# PCB_Telemetria_2020.net
KiCad netlist of a schematic drawn in EAGLE
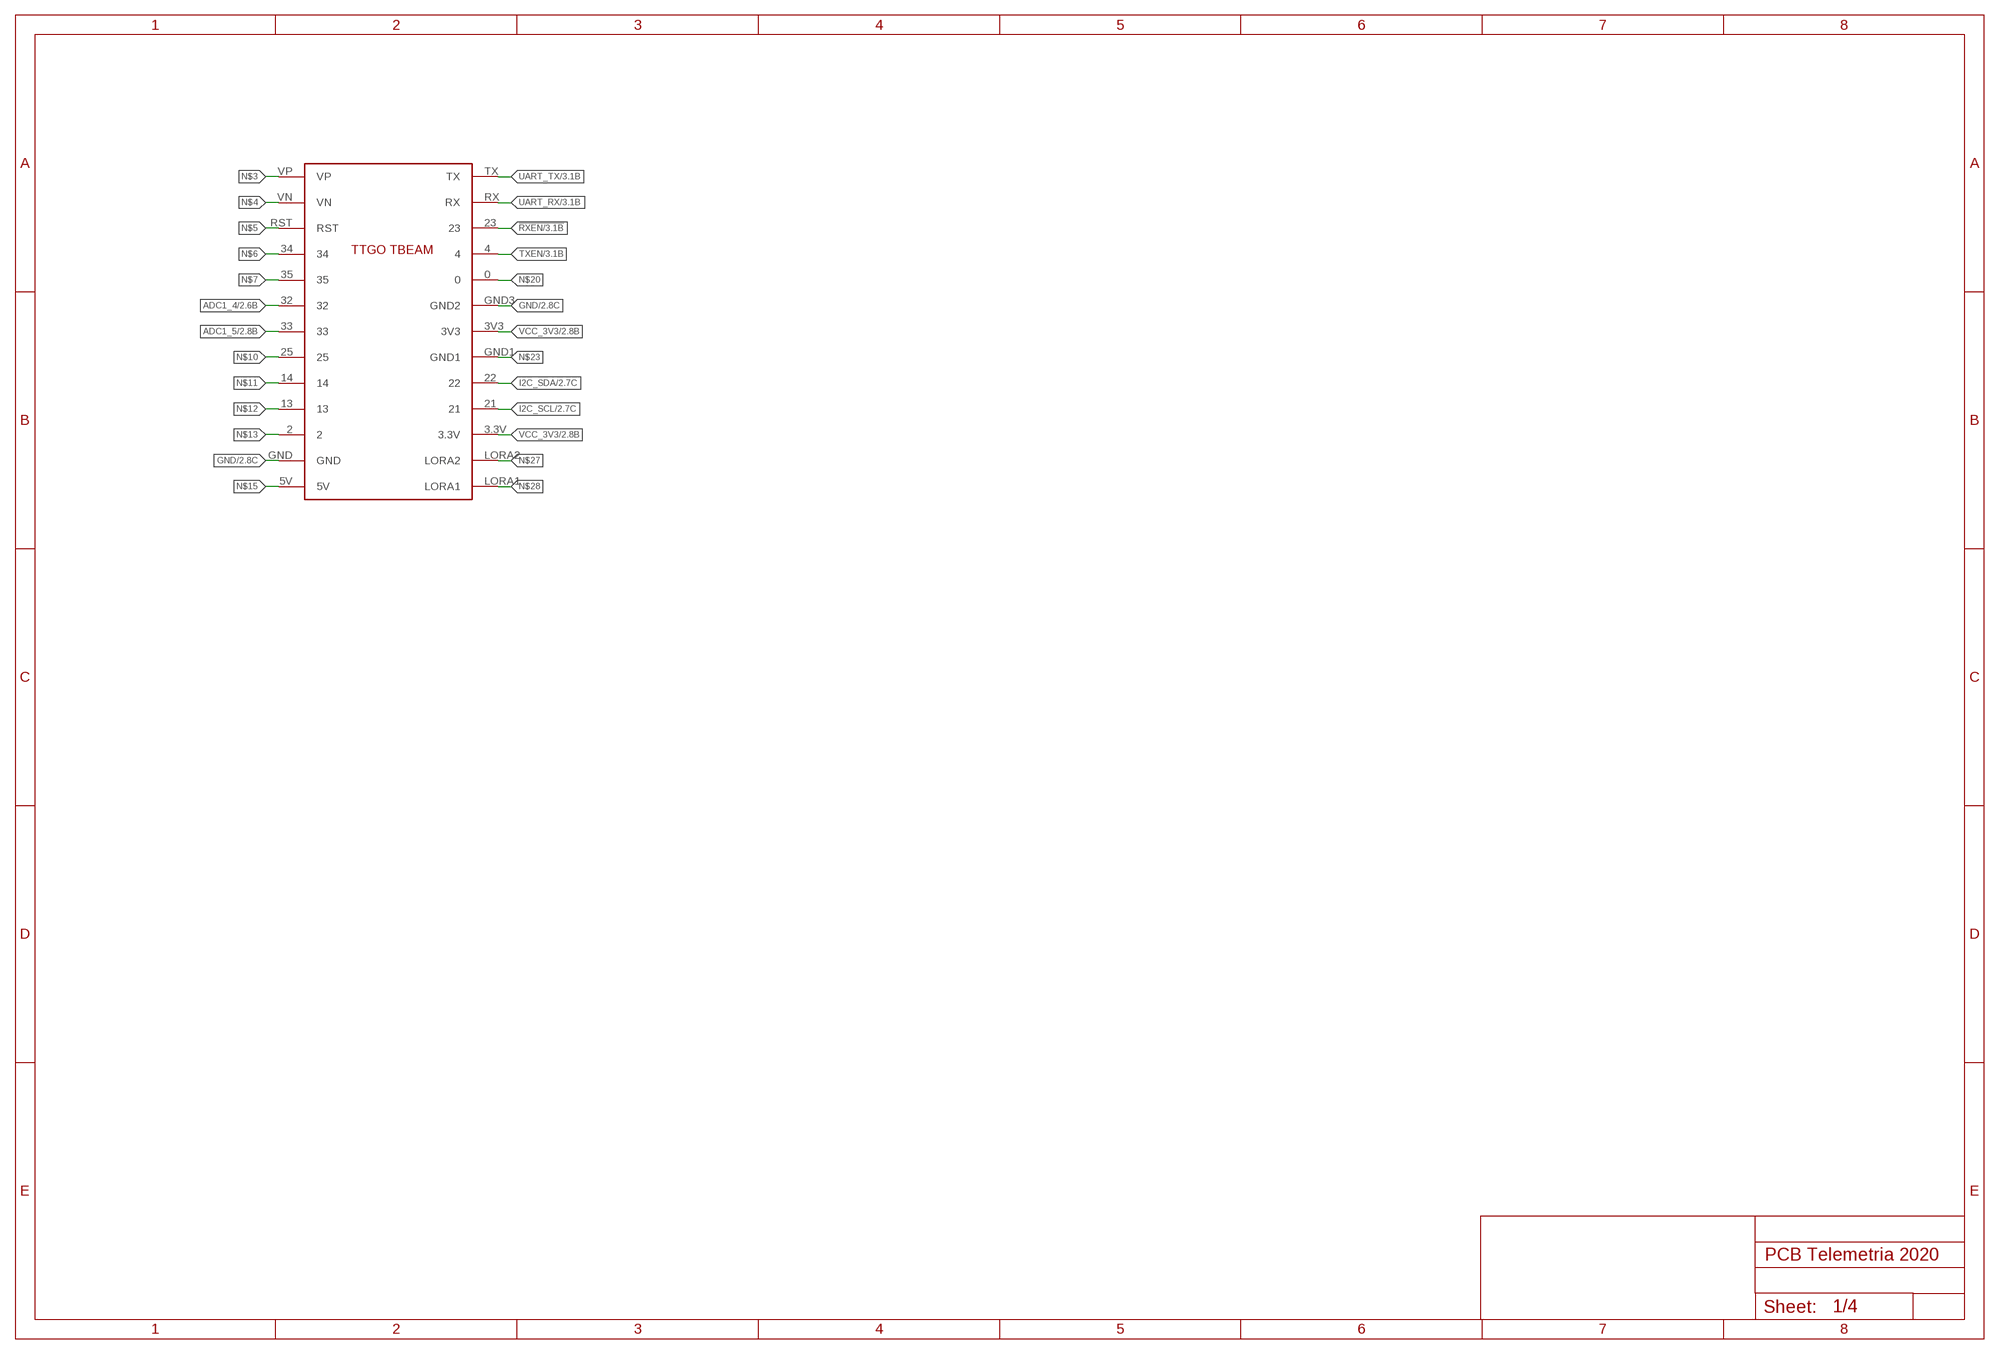
[diagram p0: schematic, sheet 1]
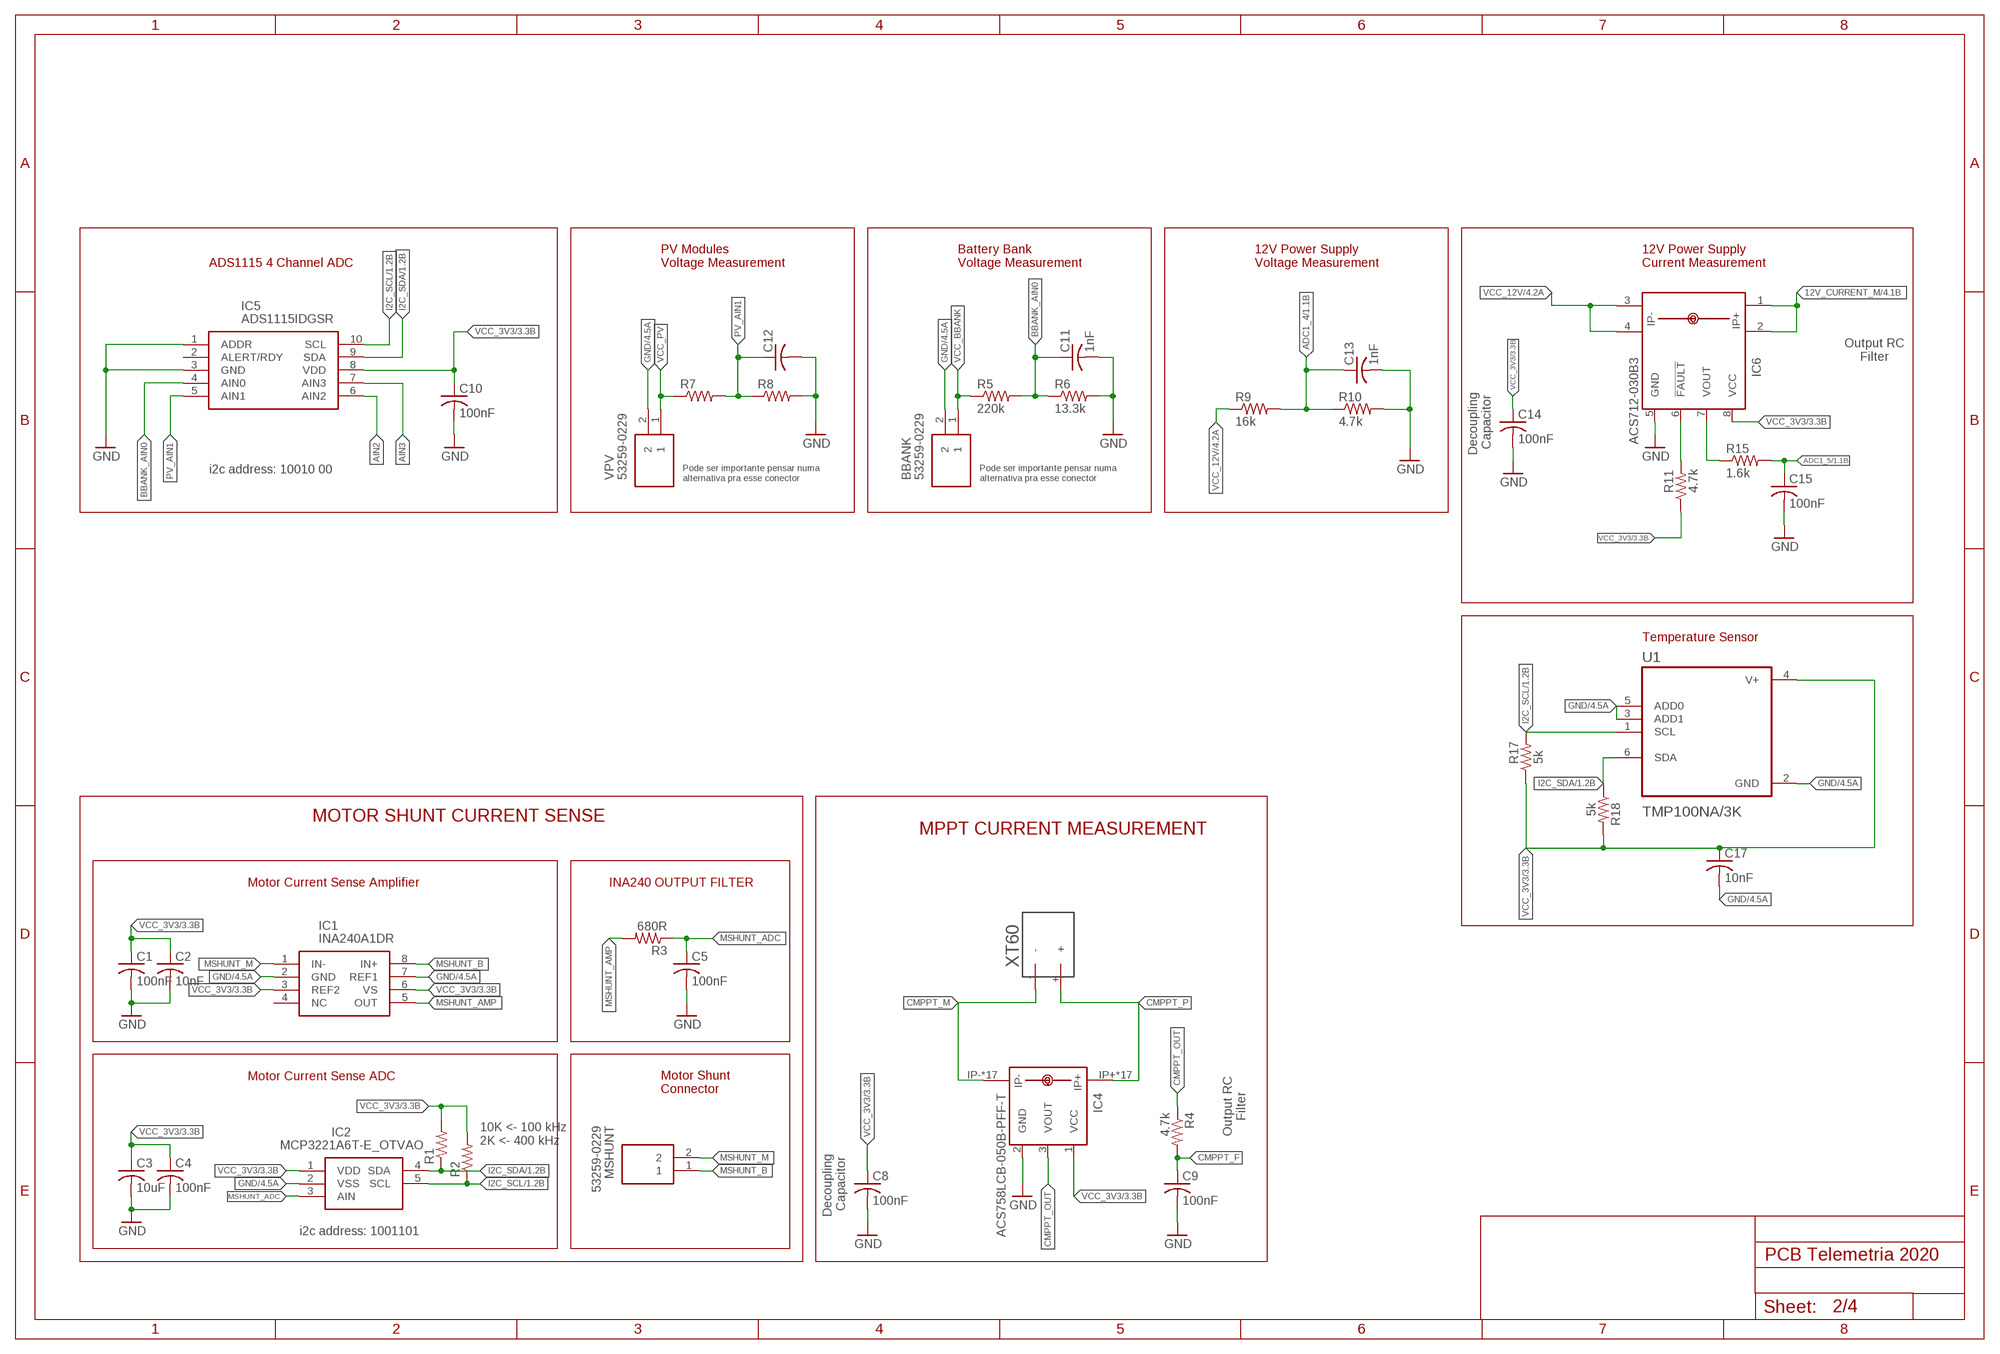
[diagram p1: schematic, sheet 2]
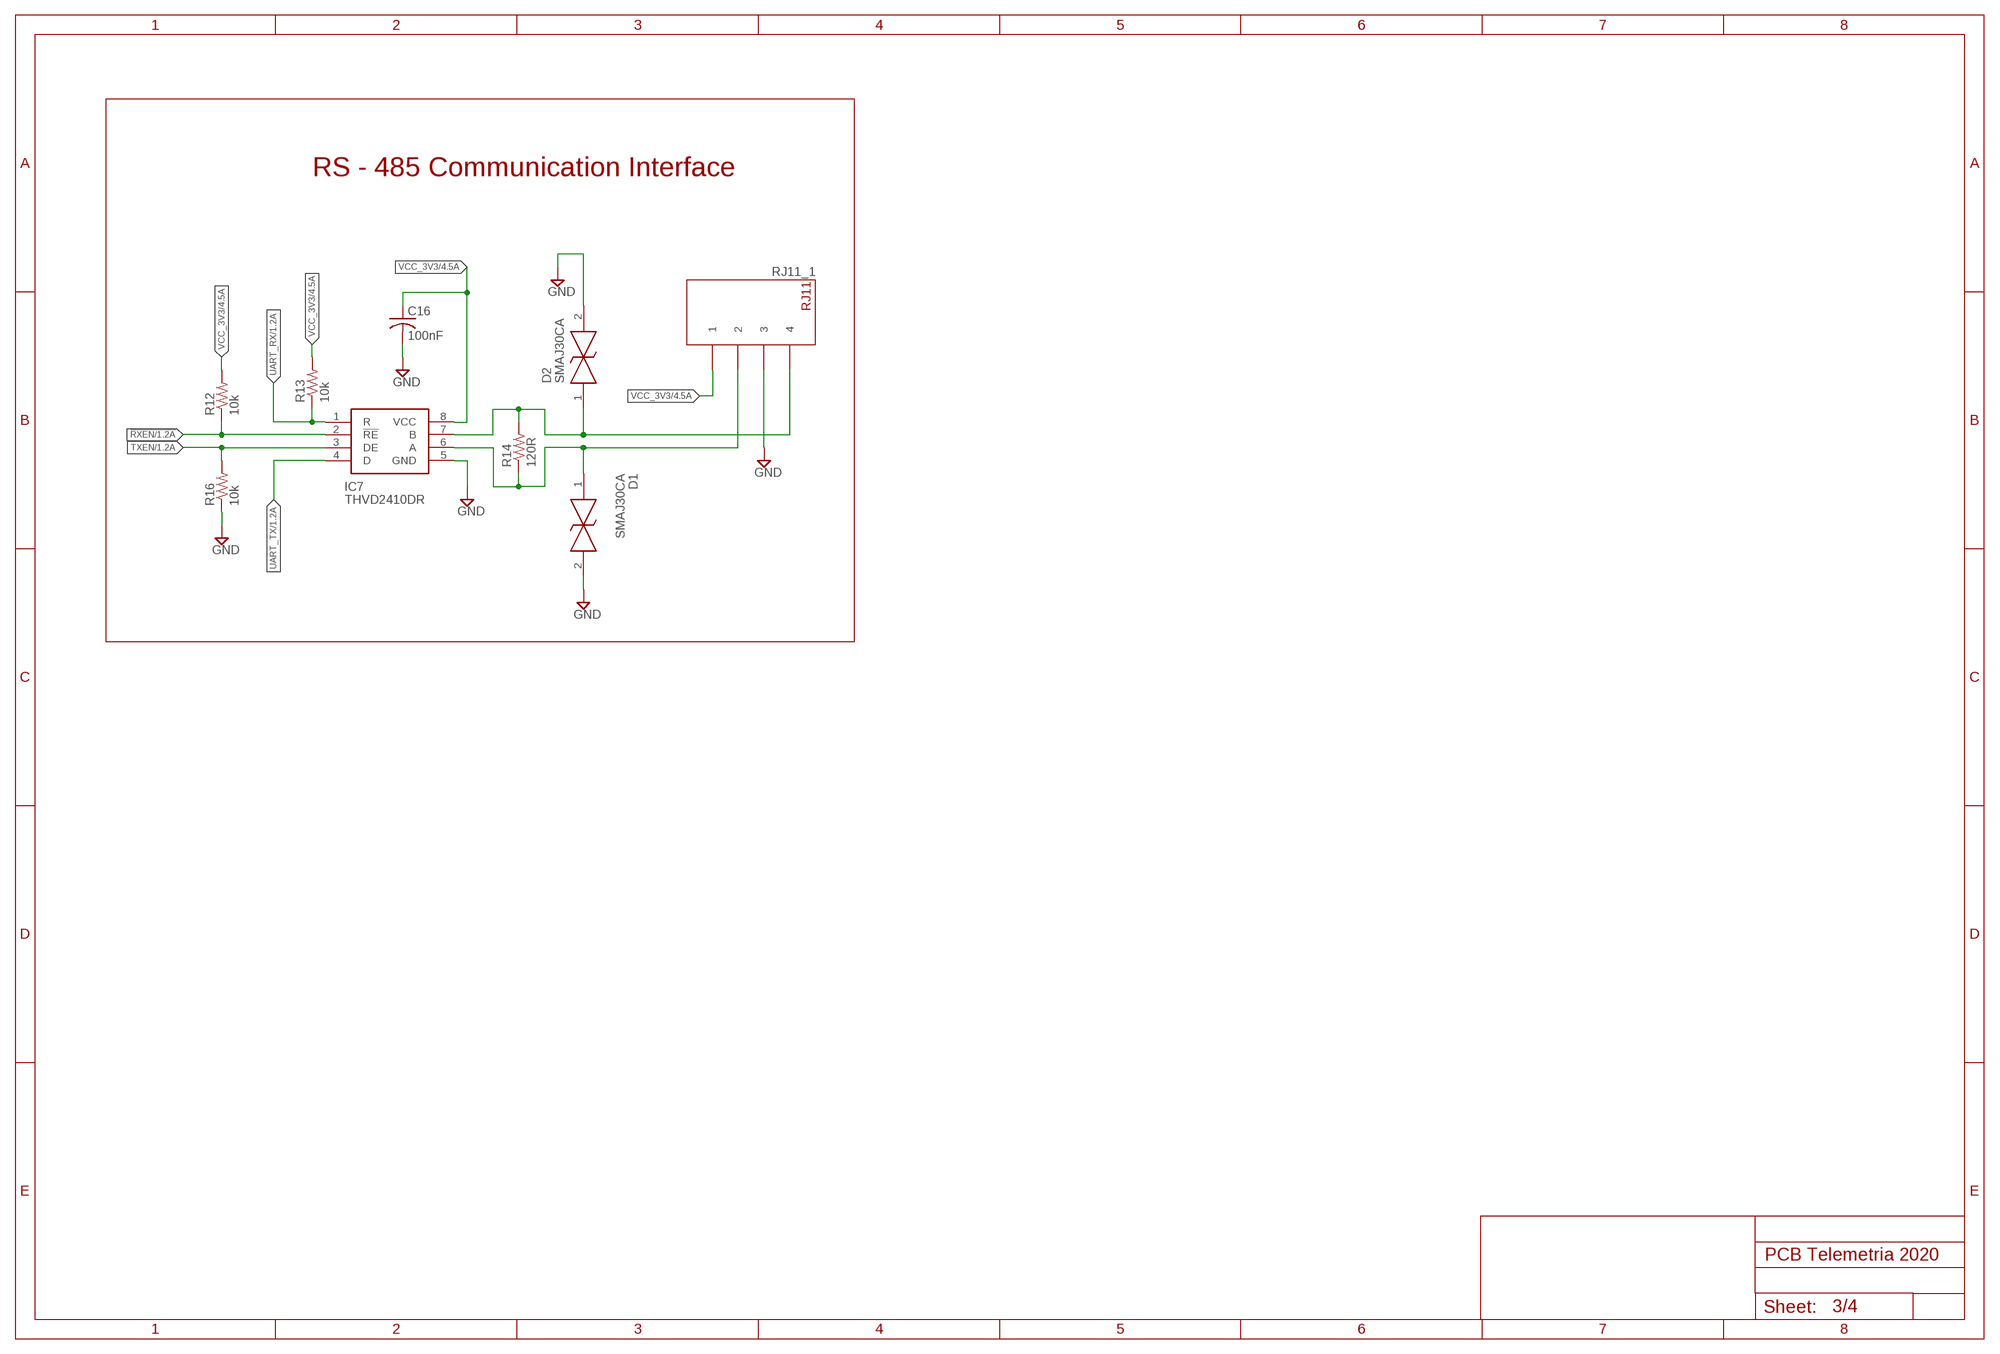
[diagram p2: schematic, sheet 3]
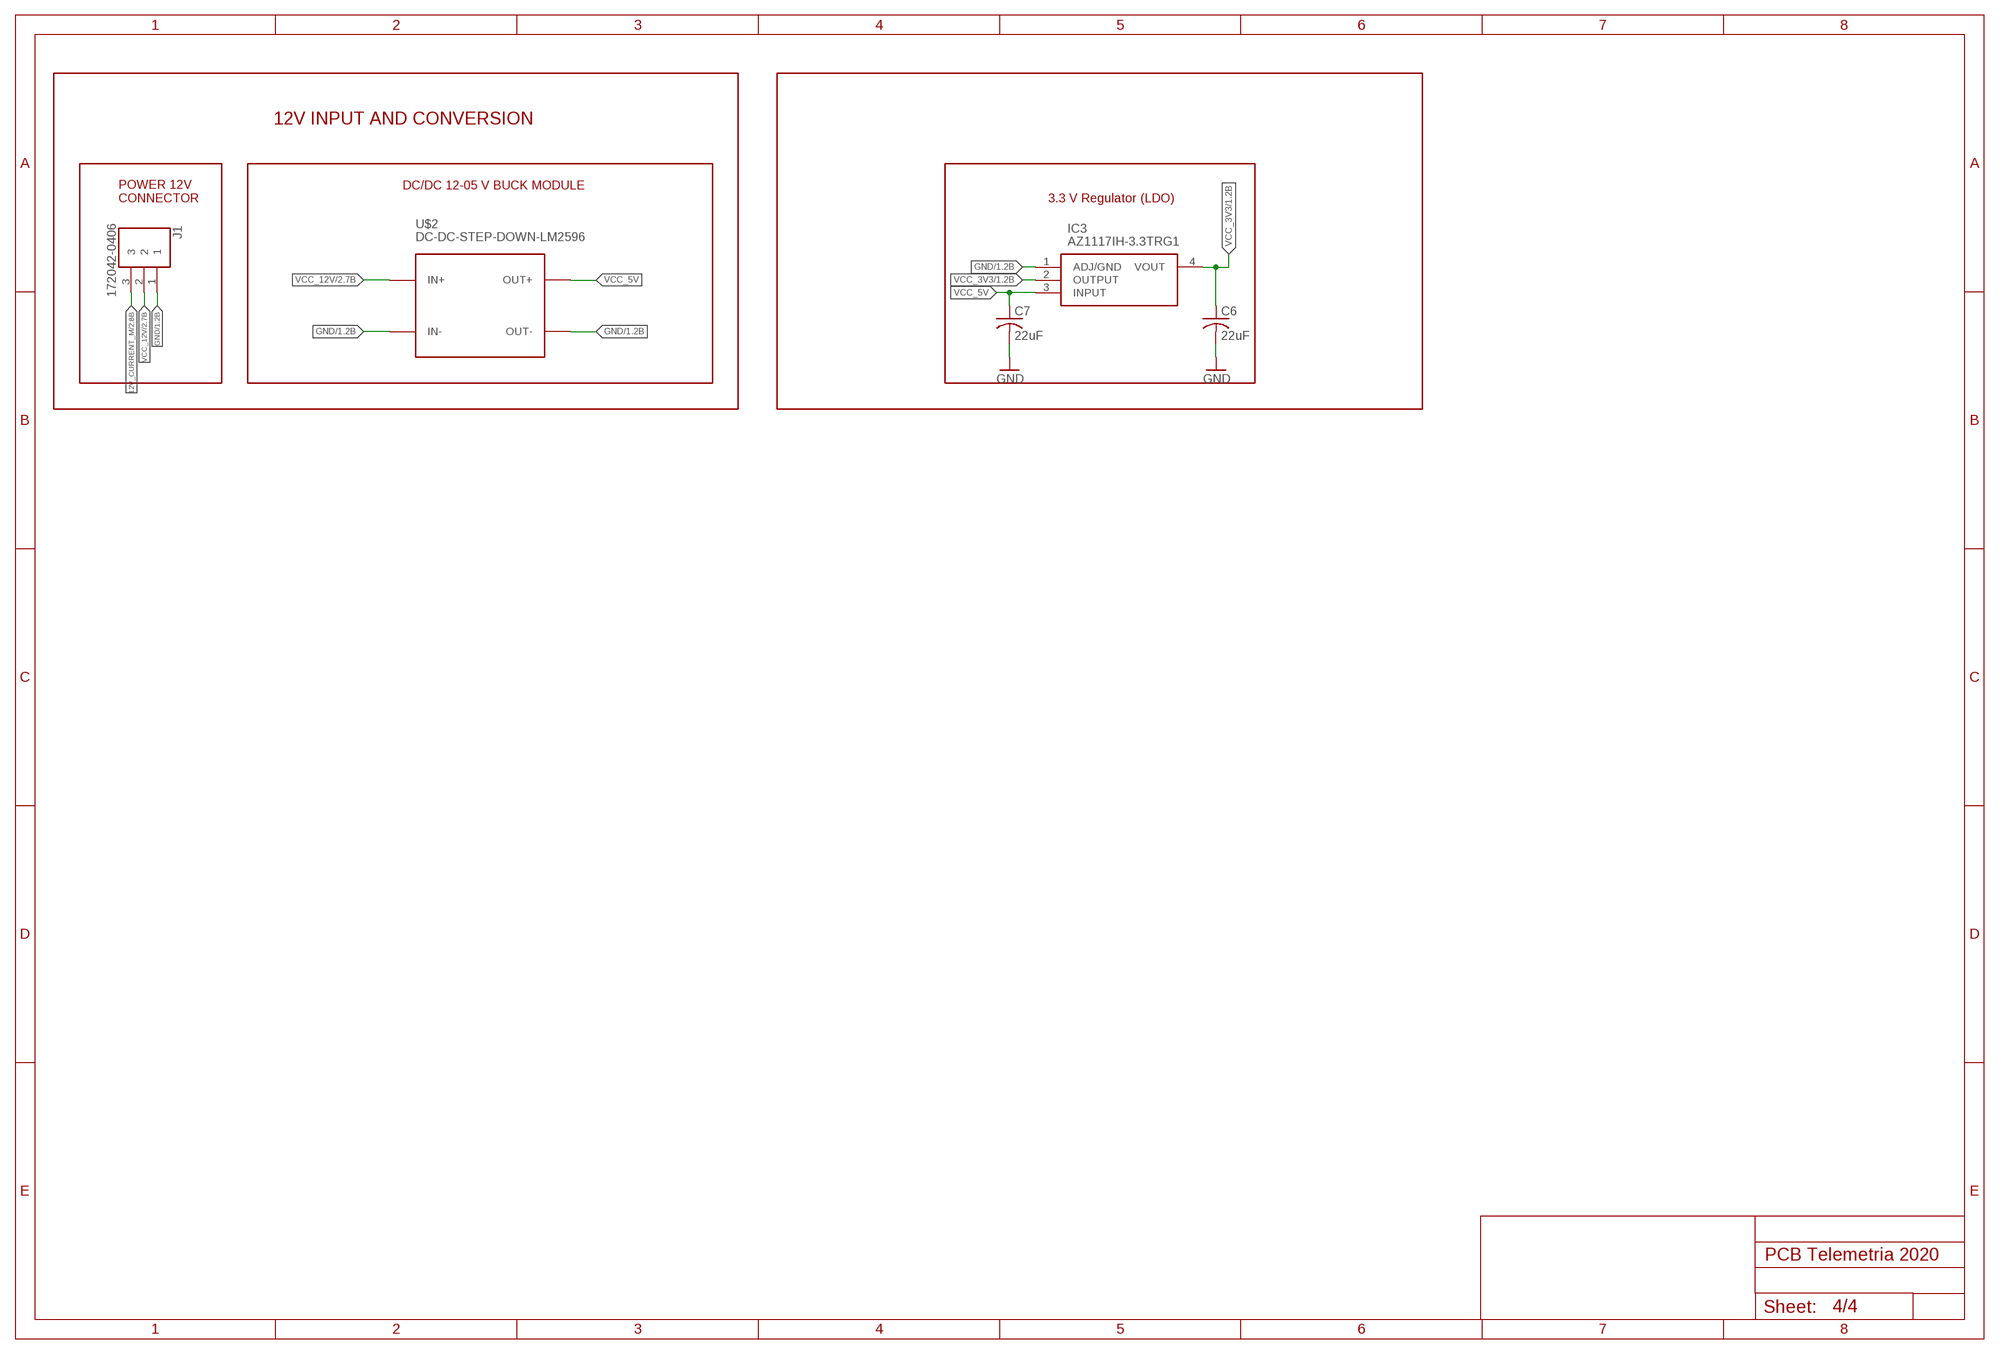
[diagram p3: schematic, sheet 4]

(export (version "E")
  (design (tool "Eeschema 10.0.6"))
  (components
    (comp (ref "BBANK")
      (value "53259-0229")
      (footprint "eagle-import:0532590229")
      (fields (field (name "MOUSER_PART_NUMBER") "538-53259-0229"))
      (libsource (lib "eagle-import") (part "53259-0229"))
    )
    (comp (ref "C1")
      (value "100nF")
      (footprint "eagle-import:C0805")
      (libsource (lib "eagle-import") (part "C-USC0805"))
    )
    (comp (ref "C2")
      (value "10nF")
      (footprint "eagle-import:C0805")
      (libsource (lib "eagle-import") (part "C-USC0805"))
    )
    (comp (ref "C3")
      (value "10uF")
      (footprint "eagle-import:C0805")
      (libsource (lib "eagle-import") (part "C-USC0805"))
    )
    (comp (ref "C4")
      (value "100nF")
      (footprint "eagle-import:C0805")
      (libsource (lib "eagle-import") (part "C-USC0805"))
    )
    (comp (ref "C5")
      (value "100nF")
      (footprint "eagle-import:C0805")
      (libsource (lib "eagle-import") (part "C-USC0805"))
    )
    (comp (ref "C8")
      (value "100nF")
      (footprint "eagle-import:C0805")
      (libsource (lib "eagle-import") (part "C-USC0805"))
    )
    (comp (ref "C9")
      (value "100nF")
      (footprint "eagle-import:C0805")
      (libsource (lib "eagle-import") (part "C-USC0805"))
    )
    (comp (ref "C10")
      (value "100nF")
      (footprint "eagle-import:C0805")
      (libsource (lib "eagle-import") (part "C-USC0805"))
    )
    (comp (ref "C11")
      (value "1nF")
      (footprint "eagle-import:C0805")
      (libsource (lib "eagle-import") (part "C-USC0805"))
    )
    (comp (ref "C12")
      (value "C-USC0805")
      (footprint "eagle-import:C0805")
      (libsource (lib "eagle-import") (part "C-USC0805"))
    )
    (comp (ref "C13")
      (value "1nF")
      (footprint "eagle-import:C0805")
      (libsource (lib "eagle-import") (part "C-USC0805"))
    )
    (comp (ref "C14")
      (value "100nF")
      (footprint "eagle-import:C0805")
      (libsource (lib "eagle-import") (part "C-USC0805"))
    )
    (comp (ref "C15")
      (value "100nF")
      (footprint "eagle-import:C0805")
      (libsource (lib "eagle-import") (part "C-USC0805"))
    )
    (comp (ref "C17")
      (value "10nF")
      (footprint "eagle-import:C0805")
      (libsource (lib "eagle-import") (part "C-USC0805"))
    )
    (comp (ref "IC1")
      (value "INA240A1DR")
      (footprint "eagle-import:SOIC127P600X175-8N")
      (fields (field (name "MOUSER_PART_NUMBER") "595-INA240A1DR"))
      (libsource (lib "eagle-import") (part "INA240A1DR"))
    )
    (comp (ref "IC2")
      (value "MCP3221A6T-E_OTVAO")
      (footprint "eagle-import:SOT95P280X145-5N")
      (fields
        (field (name "MANUFACTURER_PART_NUMBER") "MCP3221A6T-E/OTVAO")
        (field (name "MOUSER_PART_NUMBER") "579-MCP3221A6TEOTVAO")
      )
      (libsource (lib "eagle-import") (part "MCP3221A6T-E_OTVAO"))
    )
    (comp (ref "IC4")
      (value "ACS758LCB-050B-PFF-T")
      (footprint "eagle-import:CB-PFF")
      (libsource (lib "eagle-import") (part "ACS758LCB-050B-PFF-T"))
    )
    (comp (ref "IC5")
      (value "ADS1115IDGSR")
      (footprint "eagle-import:SOP50P490X110-10N")
      (fields (field (name "MOUSER_PART_NUMBER") "595-ADS1115IDGSR"))
      (libsource (lib "eagle-import") (part "ADS1115IDGSR"))
    )
    (comp (ref "IC6")
      (value "ACS712-030B3")
      (footprint "eagle-import:SOIC8")
      (libsource (lib "eagle-import") (part "ACS712-LC"))
    )
    (comp (ref "MSHUNT")
      (value "53259-0229")
      (footprint "eagle-import:0532590229")
      (fields (field (name "MOUSER_PART_NUMBER") "538-53259-0229"))
      (libsource (lib "eagle-import") (part "53259-0229"))
    )
    (comp (ref "R1")
      (value "R-US_R0805")
      (footprint "eagle-import:R0805")
      (libsource (lib "eagle-import") (part "R-US_R0805"))
    )
    (comp (ref "R2")
      (value "R-US_R0805")
      (footprint "eagle-import:R0805")
      (libsource (lib "eagle-import") (part "R-US_R0805"))
    )
    (comp (ref "R3")
      (value "680R")
      (footprint "eagle-import:R0805")
      (libsource (lib "eagle-import") (part "R-US_R0805"))
    )
    (comp (ref "R4")
      (value "4.7k")
      (footprint "eagle-import:R0805")
      (libsource (lib "eagle-import") (part "R-US_R0805"))
    )
    (comp (ref "R5")
      (value "220k")
      (footprint "eagle-import:R0805")
      (libsource (lib "eagle-import") (part "R-US_R0805"))
    )
    (comp (ref "R6")
      (value "13.3k")
      (footprint "eagle-import:R0805")
      (libsource (lib "eagle-import") (part "R-US_R0805"))
    )
    (comp (ref "R7")
      (value "R-US_R0805")
      (footprint "eagle-import:R0805")
      (libsource (lib "eagle-import") (part "R-US_R0805"))
    )
    (comp (ref "R8")
      (value "R-US_R0805")
      (footprint "eagle-import:R0805")
      (libsource (lib "eagle-import") (part "R-US_R0805"))
    )
    (comp (ref "R9")
      (value "16k")
      (footprint "eagle-import:R0805")
      (libsource (lib "eagle-import") (part "R-US_R0805"))
    )
    (comp (ref "R10")
      (value "4.7k")
      (footprint "eagle-import:R0805")
      (libsource (lib "eagle-import") (part "R-US_R0805"))
    )
    (comp (ref "R11")
      (value "4.7k")
      (footprint "eagle-import:R0805")
      (libsource (lib "eagle-import") (part "R-US_R0805"))
    )
    (comp (ref "R15")
      (value "1.6k")
      (footprint "eagle-import:R0805")
      (libsource (lib "eagle-import") (part "R-US_R0805"))
    )
    (comp (ref "R17")
      (value "5k")
      (footprint "eagle-import:R0805")
      (libsource (lib "eagle-import") (part "R-US_R0805"))
    )
    (comp (ref "R18")
      (value "5k")
      (footprint "eagle-import:R0805")
      (libsource (lib "eagle-import") (part "R-US_R0805"))
    )
    (comp (ref "U$3")
      (value "XT60")
      (footprint "eagle-import:XT60")
      (libsource (lib "eagle-import") (part "XT60"))
    )
    (comp (ref "U1")
      (value "TMP100NA/3K")
      (footprint "eagle-import:SOT95P280X145-6N")
      (fields (field (name "MF") "Texas Instruments"))
      (libsource (lib "eagle-import") (part "TMP100NA/3K"))
    )
    (comp (ref "VPV")
      (value "53259-0229")
      (footprint "eagle-import:0532590229")
      (fields (field (name "MOUSER_PART_NUMBER") "538-53259-0229"))
      (libsource (lib "eagle-import") (part "53259-0229"))
    )
    (comp (ref "U$1")
      (value "TTGOBEAM")
      (footprint "eagle-import:TTGOBEAM")
      (libsource (lib "eagle-import") (part "TTGOBEAM"))
    )
    (comp (ref "C6")
      (value "22uF")
      (footprint "eagle-import:C0805")
      (libsource (lib "eagle-import") (part "C-USC0805"))
    )
    (comp (ref "C7")
      (value "22uF")
      (footprint "eagle-import:C0805")
      (libsource (lib "eagle-import") (part "C-USC0805"))
    )
    (comp (ref "IC3")
      (value "AZ1117IH-3.3TRG1")
      (footprint "eagle-import:SOT230P700X170-4N")
      (fields (field (name "MOUSER_PART_NUMBER") "621-AZ1117IH-3.3TRG1"))
      (libsource (lib "eagle-import") (part "AZ1117IH-3.3TRG1"))
    )
    (comp (ref "J1")
      (value "172042-0406")
      (footprint "eagle-import:MOLEX_172042-0406")
      (fields (field (name "MF") "Molex") (field (name "MP") "172042-0302"))
      (libsource (lib "eagle-import") (part "172042-0406"))
    )
    (comp (ref "U$2")
      (value "DC-DC-STEP-DOWN-LM2596")
      (footprint "eagle-import:DC-DC-STEP-DOWN-LM2596")
      (libsource (lib "eagle-import") (part "DC-DC-STEP-DOWN-LM2596"))
    )
    (comp (ref "C16")
      (value "100nF")
      (footprint "eagle-import:C0805")
      (libsource (lib "eagle-import") (part "C-USC0805"))
    )
    (comp (ref "D1")
      (value "SMAJ30CA")
      (footprint "eagle-import:DIONM5026X229N")
      (fields (field (name "MOUSER_PART_NUMBER") "576-SMAJ30CA"))
      (libsource (lib "eagle-import") (part "SMAJ30CA"))
    )
    (comp (ref "D2")
      (value "SMAJ30CA")
      (footprint "eagle-import:DIONM5026X229N")
      (fields (field (name "MOUSER_PART_NUMBER") "576-SMAJ30CA"))
      (libsource (lib "eagle-import") (part "SMAJ30CA"))
    )
    (comp (ref "IC7")
      (value "THVD2410DR")
      (footprint "eagle-import:SOIC127P600X175-8N")
      (fields (field (name "MOUSER_PART_NUMBER") "595-THVD2410DR"))
      (libsource (lib "eagle-import") (part "THVD2410DR"))
    )
    (comp (ref "R12")
      (value "10k")
      (footprint "eagle-import:M0805")
      (libsource (lib "eagle-import") (part "R-US_M0805"))
    )
    (comp (ref "R13")
      (value "10k")
      (footprint "eagle-import:M0805")
      (libsource (lib "eagle-import") (part "R-US_M0805"))
    )
    (comp (ref "R14")
      (value "120R")
      (footprint "eagle-import:M0805")
      (libsource (lib "eagle-import") (part "R-US_M0805"))
    )
    (comp (ref "R16")
      (value "10k")
      (footprint "eagle-import:M0805")
      (libsource (lib "eagle-import") (part "R-US_M0805"))
    )
    (comp (ref "RJ11_1")
      (value "TFC44")
      (footprint "eagle-import:TFC44")
      (libsource (lib "eagle-import") (part "TFC44"))
    )
  )
  (nets
    (net (code "1") (name "12V_CURRENT_M") (class "Default")
      (node (ref "IC6") (pin "1") (pinfunction "IP+_1") (pintype "passive"))
      (node (ref "IC6") (pin "2") (pinfunction "IP+1_2") (pintype "passive"))
      (node (ref "J1") (pin "3") (pinfunction "3_3") (pintype "passive"))
    )
    (net (code "2") (name "ADC1_4") (class "Default")
      (node (ref "C13") (pin "1") (pinfunction "1_1") (pintype "passive"))
      (node (ref "R10") (pin "1") (pinfunction "1_1") (pintype "passive"))
      (node (ref "R9") (pin "2") (pinfunction "2_2") (pintype "passive"))
      (node (ref "U$1") (pin "32") (pinfunction "32_32") (pintype "bidirectional"))
    )
    (net (code "3") (name "ADC1_5") (class "Default")
      (node (ref "C15") (pin "1") (pinfunction "1_1") (pintype "passive"))
      (node (ref "R15") (pin "2") (pinfunction "2_2") (pintype "passive"))
      (node (ref "U$1") (pin "33") (pinfunction "33_33") (pintype "bidirectional"))
    )
    (net (code "4") (name "AIN2") (class "Default")
      (node (ref "IC5") (pin "6") (pinfunction "AIN2_6") (pintype "bidirectional"))
    )
    (net (code "5") (name "AIN3") (class "Default")
      (node (ref "IC5") (pin "7") (pinfunction "AIN3_7") (pintype "bidirectional"))
    )
    (net (code "6") (name "BBANK_AIN0") (class "Default")
      (node (ref "C11") (pin "1") (pinfunction "1_1") (pintype "passive"))
      (node (ref "IC5") (pin "4") (pinfunction "AIN0_4") (pintype "bidirectional"))
      (node (ref "R5") (pin "2") (pinfunction "2_2") (pintype "passive"))
      (node (ref "R6") (pin "1") (pinfunction "1_1") (pintype "passive"))
    )
    (net (code "7") (name "CMPPT_F") (class "Default")
      (node (ref "C9") (pin "1") (pinfunction "1_1") (pintype "passive"))
      (node (ref "R4") (pin "2") (pinfunction "2_2") (pintype "passive"))
    )
    (net (code "8") (name "CMPPT_M") (class "Default")
      (node (ref "IC4") (pin "IP-") (pinfunction "IP-_IP-") (pintype "passive"))
      (node (ref "IC4") (pin "IP-@10") (pinfunction "IP-_IP-@10") (pintype "passive"))
      (node (ref "IC4") (pin "IP-@11") (pinfunction "IP-_IP-@11") (pintype "passive"))
      (node (ref "IC4") (pin "IP-@12") (pinfunction "IP-_IP-@12") (pintype "passive"))
      (node (ref "IC4") (pin "IP-@13") (pinfunction "IP-_IP-@13") (pintype "passive"))
      (node (ref "IC4") (pin "IP-@14") (pinfunction "IP-_IP-@14") (pintype "passive"))
      (node (ref "IC4") (pin "IP-@15") (pinfunction "IP-_IP-@15") (pintype "passive"))
      (node (ref "IC4") (pin "IP-@16") (pinfunction "IP-_IP-@16") (pintype "passive"))
      (node (ref "IC4") (pin "IP-@17") (pinfunction "IP-_IP-@17") (pintype "passive"))
      (node (ref "IC4") (pin "IP-@2") (pinfunction "IP-_IP-@2") (pintype "passive"))
      (node (ref "IC4") (pin "IP-@3") (pinfunction "IP-_IP-@3") (pintype "passive"))
      (node (ref "IC4") (pin "IP-@4") (pinfunction "IP-_IP-@4") (pintype "passive"))
      (node (ref "IC4") (pin "IP-@5") (pinfunction "IP-_IP-@5") (pintype "passive"))
      (node (ref "IC4") (pin "IP-@6") (pinfunction "IP-_IP-@6") (pintype "passive"))
      (node (ref "IC4") (pin "IP-@7") (pinfunction "IP-_IP-@7") (pintype "passive"))
      (node (ref "IC4") (pin "IP-@8") (pinfunction "IP-_IP-@8") (pintype "passive"))
      (node (ref "IC4") (pin "IP-@9") (pinfunction "IP-_IP-@9") (pintype "passive"))
      (node (ref "U$3") (pin "-") (pinfunction "-_-") (pintype "bidirectional"))
    )
    (net (code "9") (name "CMPPT_OUT") (class "Default")
      (node (ref "IC4") (pin "3") (pinfunction "VOUT_3") (pintype "output"))
      (node (ref "R4") (pin "1") (pinfunction "1_1") (pintype "passive"))
    )
    (net (code "10") (name "CMPPT_P") (class "Default")
      (node (ref "IC4") (pin "IP+") (pinfunction "IP+_IP+") (pintype "passive"))
      (node (ref "IC4") (pin "IP+@10") (pinfunction "IP+_IP+@10") (pintype "passive"))
      (node (ref "IC4") (pin "IP+@11") (pinfunction "IP+_IP+@11") (pintype "passive"))
      (node (ref "IC4") (pin "IP+@12") (pinfunction "IP+_IP+@12") (pintype "passive"))
      (node (ref "IC4") (pin "IP+@13") (pinfunction "IP+_IP+@13") (pintype "passive"))
      (node (ref "IC4") (pin "IP+@14") (pinfunction "IP+_IP+@14") (pintype "passive"))
      (node (ref "IC4") (pin "IP+@15") (pinfunction "IP+_IP+@15") (pintype "passive"))
      (node (ref "IC4") (pin "IP+@16") (pinfunction "IP+_IP+@16") (pintype "passive"))
      (node (ref "IC4") (pin "IP+@17") (pinfunction "IP+_IP+@17") (pintype "passive"))
      (node (ref "IC4") (pin "IP+@2") (pinfunction "IP+_IP+@2") (pintype "passive"))
      (node (ref "IC4") (pin "IP+@3") (pinfunction "IP+_IP+@3") (pintype "passive"))
      (node (ref "IC4") (pin "IP+@4") (pinfunction "IP+_IP+@4") (pintype "passive"))
      (node (ref "IC4") (pin "IP+@5") (pinfunction "IP+_IP+@5") (pintype "passive"))
      (node (ref "IC4") (pin "IP+@6") (pinfunction "IP+_IP+@6") (pintype "passive"))
      (node (ref "IC4") (pin "IP+@7") (pinfunction "IP+_IP+@7") (pintype "passive"))
      (node (ref "IC4") (pin "IP+@8") (pinfunction "IP+_IP+@8") (pintype "passive"))
      (node (ref "IC4") (pin "IP+@9") (pinfunction "IP+_IP+@9") (pintype "passive"))
      (node (ref "U$3") (pin "+") (pinfunction "+_+") (pintype "bidirectional"))
    )
    (net (code "11") (name "GND") (class "Default")
      (node (ref "BBANK") (pin "2") (pinfunction "2_2") (pintype "bidirectional"))
      (node (ref "C1") (pin "2") (pinfunction "2_2") (pintype "passive"))
      (node (ref "C10") (pin "2") (pinfunction "2_2") (pintype "passive"))
      (node (ref "C11") (pin "2") (pinfunction "2_2") (pintype "passive"))
      (node (ref "C12") (pin "2") (pinfunction "2_2") (pintype "passive"))
      (node (ref "C13") (pin "2") (pinfunction "2_2") (pintype "passive"))
      (node (ref "C14") (pin "2") (pinfunction "2_2") (pintype "passive"))
      (node (ref "C15") (pin "2") (pinfunction "2_2") (pintype "passive"))
      (node (ref "C16") (pin "2") (pinfunction "2_2") (pintype "passive"))
      (node (ref "C17") (pin "2") (pinfunction "2_2") (pintype "passive"))
      (node (ref "C2") (pin "2") (pinfunction "2_2") (pintype "passive"))
      (node (ref "C3") (pin "2") (pinfunction "2_2") (pintype "passive"))
      (node (ref "C4") (pin "2") (pinfunction "2_2") (pintype "passive"))
      (node (ref "C5") (pin "2") (pinfunction "2_2") (pintype "passive"))
      (node (ref "C6") (pin "2") (pinfunction "2_2") (pintype "passive"))
      (node (ref "C7") (pin "2") (pinfunction "2_2") (pintype "passive"))
      (node (ref "C8") (pin "2") (pinfunction "2_2") (pintype "passive"))
      (node (ref "C9") (pin "2") (pinfunction "2_2") (pintype "passive"))
      (node (ref "D1") (pin "2") (pinfunction "2_2") (pintype "bidirectional"))
      (node (ref "D2") (pin "2") (pinfunction "2_2") (pintype "bidirectional"))
      (node (ref "IC1") (pin "2") (pinfunction "GND_2") (pintype "bidirectional"))
      (node (ref "IC1") (pin "7") (pinfunction "REF1_7") (pintype "bidirectional"))
      (node (ref "IC2") (pin "2") (pinfunction "VSS_2") (pintype "bidirectional"))
      (node (ref "IC3") (pin "1") (pinfunction "ADJ/GND_1") (pintype "bidirectional"))
      (node (ref "IC4") (pin "2") (pinfunction "GND_2") (pintype "power_in"))
      (node (ref "IC5") (pin "1") (pinfunction "ADDR_1") (pintype "bidirectional"))
      (node (ref "IC5") (pin "3") (pinfunction "GND_3") (pintype "bidirectional"))
      (node (ref "IC6") (pin "5") (pinfunction "GND_5") (pintype "power_in"))
      (node (ref "IC7") (pin "5") (pinfunction "GND_5") (pintype "bidirectional"))
      (node (ref "J1") (pin "1") (pinfunction "1_1") (pintype "passive"))
      (node (ref "R10") (pin "2") (pinfunction "2_2") (pintype "passive"))
      (node (ref "R16") (pin "1") (pinfunction "1_1") (pintype "passive"))
      (node (ref "R6") (pin "2") (pinfunction "2_2") (pintype "passive"))
      (node (ref "R8") (pin "2") (pinfunction "2_2") (pintype "passive"))
      (node (ref "RJ11_1") (pin "P$3") (pinfunction "3_P$3") (pintype "bidirectional"))
      (node (ref "U$1") (pin "GND") (pinfunction "GND_GND") (pintype "bidirectional"))
      (node (ref "U$1") (pin "GND3") (pinfunction "GND2_GND3") (pintype "bidirectional"))
      (node (ref "U$2") (pin "IN-") (pinfunction "IN-_IN-") (pintype "bidirectional"))
      (node (ref "U$2") (pin "OUT-") (pinfunction "OUT-_OUT-") (pintype "bidirectional"))
      (node (ref "U1") (pin "2") (pinfunction "GND_2") (pintype "power_in"))
      (node (ref "U1") (pin "3") (pinfunction "ADD1_3") (pintype "input"))
      (node (ref "U1") (pin "5") (pinfunction "ADD0_5") (pintype "input"))
      (node (ref "VPV") (pin "2") (pinfunction "2_2") (pintype "bidirectional"))
    )
    (net (code "12") (name "I2C_SCL") (class "Default")
      (node (ref "IC2") (pin "5") (pinfunction "SCL_5") (pintype "bidirectional"))
      (node (ref "IC5") (pin "10") (pinfunction "SCL_10") (pintype "bidirectional"))
      (node (ref "R17") (pin "2") (pinfunction "2_2") (pintype "passive"))
      (node (ref "R2") (pin "1") (pinfunction "1_1") (pintype "passive"))
      (node (ref "U$1") (pin "21") (pinfunction "21_21") (pintype "bidirectional"))
      (node (ref "U1") (pin "1") (pinfunction "SCL_1") (pintype "input"))
    )
    (net (code "13") (name "I2C_SDA") (class "Default")
      (node (ref "IC2") (pin "4") (pinfunction "SDA_4") (pintype "bidirectional"))
      (node (ref "IC5") (pin "9") (pinfunction "SDA_9") (pintype "bidirectional"))
      (node (ref "R1") (pin "1") (pinfunction "1_1") (pintype "passive"))
      (node (ref "R18") (pin "1") (pinfunction "1_1") (pintype "passive"))
      (node (ref "U$1") (pin "22") (pinfunction "22_22") (pintype "bidirectional"))
      (node (ref "U1") (pin "6") (pinfunction "SDA_6") (pintype "bidirectional"))
    )
    (net (code "14") (name "MSHUNT_ADC") (class "Default")
      (node (ref "C5") (pin "1") (pinfunction "1_1") (pintype "passive"))
      (node (ref "IC2") (pin "3") (pinfunction "AIN_3") (pintype "bidirectional"))
      (node (ref "R3") (pin "1") (pinfunction "1_1") (pintype "passive"))
    )
    (net (code "15") (name "MSHUNT_AMP") (class "Default")
      (node (ref "IC1") (pin "5") (pinfunction "OUT_5") (pintype "bidirectional"))
      (node (ref "R3") (pin "2") (pinfunction "2_2") (pintype "passive"))
    )
    (net (code "16") (name "MSHUNT_B") (class "Default")
      (node (ref "IC1") (pin "8") (pinfunction "IN+_8") (pintype "bidirectional"))
      (node (ref "MSHUNT") (pin "1") (pinfunction "1_1") (pintype "bidirectional"))
    )
    (net (code "17") (name "MSHUNT_M") (class "Default")
      (node (ref "IC1") (pin "1") (pinfunction "IN-_1") (pintype "bidirectional"))
      (node (ref "MSHUNT") (pin "2") (pinfunction "2_2") (pintype "bidirectional"))
    )
    (net (code "18") (name "N$3") (class "Default")
      (node (ref "U$1") (pin "VP") (pinfunction "VP_VP") (pintype "bidirectional"))
    )
    (net (code "19") (name "N$4") (class "Default")
      (node (ref "U$1") (pin "VN") (pinfunction "VN_VN") (pintype "bidirectional"))
    )
    (net (code "20") (name "N$5") (class "Default")
      (node (ref "U$1") (pin "RST") (pinfunction "RST_RST") (pintype "bidirectional"))
    )
    (net (code "21") (name "N$6") (class "Default")
      (node (ref "U$1") (pin "34") (pinfunction "34_34") (pintype "bidirectional"))
    )
    (net (code "22") (name "N$7") (class "Default")
      (node (ref "U$1") (pin "35") (pinfunction "35_35") (pintype "bidirectional"))
    )
    (net (code "23") (name "N$10") (class "Default")
      (node (ref "U$1") (pin "25") (pinfunction "25_25") (pintype "bidirectional"))
    )
    (net (code "24") (name "N$11") (class "Default")
      (node (ref "U$1") (pin "14") (pinfunction "14_14") (pintype "bidirectional"))
    )
    (net (code "25") (name "N$12") (class "Default")
      (node (ref "U$1") (pin "13") (pinfunction "13_13") (pintype "bidirectional"))
    )
    (net (code "26") (name "N$13") (class "Default")
      (node (ref "U$1") (pin "2") (pinfunction "2_2") (pintype "bidirectional"))
    )
    (net (code "27") (name "N$15") (class "Default")
      (node (ref "U$1") (pin "5V") (pinfunction "5V_5V") (pintype "bidirectional"))
    )
    (net (code "28") (name "N$20") (class "Default")
      (node (ref "U$1") (pin "0") (pinfunction "0_0") (pintype "bidirectional"))
    )
    (net (code "29") (name "N$23") (class "Default")
      (node (ref "U$1") (pin "GND1") (pinfunction "GND1_GND1") (pintype "bidirectional"))
    )
    (net (code "30") (name "N$27") (class "Default")
      (node (ref "U$1") (pin "LORA2") (pinfunction "LORA2_LORA2") (pintype "bidirectional"))
    )
    (net (code "31") (name "N$28") (class "Default")
      (node (ref "U$1") (pin "LORA1") (pinfunction "LORA1_LORA1") (pintype "bidirectional"))
    )
    (net (code "32") (name "Net-(IC6-VOUT)") (class "Default")
      (node (ref "IC6") (pin "7") (pinfunction "VOUT_7") (pintype "output"))
      (node (ref "R15") (pin "1") (pinfunction "1_1") (pintype "passive"))
    )
    (net (code "33") (name "Net-(IC6-~{FAULT})") (class "Default")
      (node (ref "IC6") (pin "6") (pinfunction "~{FAULT}_6") (pintype "bidirectional"))
      (node (ref "R11") (pin "2") (pinfunction "2_2") (pintype "passive"))
    )
    (net (code "34") (name "Net-(IC7-A)") (class "Default")
      (node (ref "D1") (pin "1") (pinfunction "1_1") (pintype "bidirectional"))
      (node (ref "IC7") (pin "6") (pinfunction "A_6") (pintype "bidirectional"))
      (node (ref "R14") (pin "1") (pinfunction "1_1") (pintype "passive"))
      (node (ref "RJ11_1") (pin "P$2") (pinfunction "2_P$2") (pintype "bidirectional"))
    )
    (net (code "35") (name "Net-(IC7-B)") (class "Default")
      (node (ref "D2") (pin "1") (pinfunction "1_1") (pintype "bidirectional"))
      (node (ref "IC7") (pin "7") (pinfunction "B_7") (pintype "bidirectional"))
      (node (ref "R14") (pin "2") (pinfunction "2_2") (pintype "passive"))
      (node (ref "RJ11_1") (pin "P$4") (pinfunction "4_P$4") (pintype "bidirectional"))
    )
    (net (code "36") (name "PV_AIN1") (class "Default")
      (node (ref "C12") (pin "1") (pinfunction "1_1") (pintype "passive"))
      (node (ref "IC5") (pin "5") (pinfunction "AIN1_5") (pintype "bidirectional"))
      (node (ref "R7") (pin "2") (pinfunction "2_2") (pintype "passive"))
      (node (ref "R8") (pin "1") (pinfunction "1_1") (pintype "passive"))
    )
    (net (code "37") (name "TXEN") (class "Default")
      (node (ref "IC7") (pin "3") (pinfunction "DE_3") (pintype "bidirectional"))
      (node (ref "R16") (pin "2") (pinfunction "2_2") (pintype "passive"))
      (node (ref "U$1") (pin "4") (pinfunction "4_4") (pintype "bidirectional"))
    )
    (net (code "38") (name "UART_RX") (class "Default")
      (node (ref "IC7") (pin "1") (pinfunction "R_1") (pintype "bidirectional"))
      (node (ref "R13") (pin "1") (pinfunction "1_1") (pintype "passive"))
      (node (ref "U$1") (pin "RX") (pinfunction "RX_RX") (pintype "bidirectional"))
    )
    (net (code "39") (name "UART_TX") (class "Default")
      (node (ref "IC7") (pin "4") (pinfunction "D_4") (pintype "bidirectional"))
      (node (ref "U$1") (pin "TX") (pinfunction "TX_TX") (pintype "bidirectional"))
    )
    (net (code "40") (name "VCC_3V3") (class "Default")
      (node (ref "C1") (pin "1") (pinfunction "1_1") (pintype "passive"))
      (node (ref "C10") (pin "1") (pinfunction "1_1") (pintype "passive"))
      (node (ref "C14") (pin "1") (pinfunction "1_1") (pintype "passive"))
      (node (ref "C16") (pin "1") (pinfunction "1_1") (pintype "passive"))
      (node (ref "C17") (pin "1") (pinfunction "1_1") (pintype "passive"))
      (node (ref "C2") (pin "1") (pinfunction "1_1") (pintype "passive"))
      (node (ref "C3") (pin "1") (pinfunction "1_1") (pintype "passive"))
      (node (ref "C4") (pin "1") (pinfunction "1_1") (pintype "passive"))
      (node (ref "C6") (pin "1") (pinfunction "1_1") (pintype "passive"))
      (node (ref "C8") (pin "1") (pinfunction "1_1") (pintype "passive"))
      (node (ref "IC1") (pin "3") (pinfunction "REF2_3") (pintype "bidirectional"))
      (node (ref "IC1") (pin "6") (pinfunction "VS_6") (pintype "bidirectional"))
      (node (ref "IC2") (pin "1") (pinfunction "VDD_1") (pintype "bidirectional"))
      (node (ref "IC3") (pin "2") (pinfunction "OUTPUT_2") (pintype "bidirectional"))
      (node (ref "IC3") (pin "4") (pinfunction "VOUT_4") (pintype "bidirectional"))
      (node (ref "IC4") (pin "1") (pinfunction "VCC_1") (pintype "power_in"))
      (node (ref "IC5") (pin "8") (pinfunction "VDD_8") (pintype "bidirectional"))
      (node (ref "IC6") (pin "8") (pinfunction "VCC_8") (pintype "power_in"))
      (node (ref "IC7") (pin "8") (pinfunction "VCC_8") (pintype "bidirectional"))
      (node (ref "R1") (pin "2") (pinfunction "2_2") (pintype "passive"))
      (node (ref "R11") (pin "1") (pinfunction "1_1") (pintype "passive"))
      (node (ref "R12") (pin "2") (pinfunction "2_2") (pintype "passive"))
      (node (ref "R13") (pin "2") (pinfunction "2_2") (pintype "passive"))
      (node (ref "R17") (pin "1") (pinfunction "1_1") (pintype "passive"))
      (node (ref "R18") (pin "2") (pinfunction "2_2") (pintype "passive"))
      (node (ref "R2") (pin "2") (pinfunction "2_2") (pintype "passive"))
      (node (ref "RJ11_1") (pin "P$1") (pinfunction "1_P$1") (pintype "bidirectional"))
      (node (ref "U$1") (pin "3.3V") (pinfunction "3.3V_3.3V") (pintype "bidirectional"))
      (node (ref "U$1") (pin "3V3") (pinfunction "3V3_3V3") (pintype "bidirectional"))
      (node (ref "U1") (pin "4") (pinfunction "V+_4") (pintype "power_in"))
    )
    (net (code "41") (name "VCC_5V") (class "Default")
      (node (ref "C7") (pin "1") (pinfunction "1_1") (pintype "passive"))
      (node (ref "IC3") (pin "3") (pinfunction "INPUT_3") (pintype "bidirectional"))
      (node (ref "U$2") (pin "OUT+") (pinfunction "OUT+_OUT+") (pintype "bidirectional"))
    )
    (net (code "42") (name "VCC_12V") (class "Default")
      (node (ref "IC6") (pin "3") (pinfunction "IP-_3") (pintype "passive"))
      (node (ref "IC6") (pin "4") (pinfunction "IP-1_4") (pintype "passive"))
      (node (ref "J1") (pin "2") (pinfunction "2_2") (pintype "passive"))
      (node (ref "R9") (pin "1") (pinfunction "1_1") (pintype "passive"))
      (node (ref "U$2") (pin "IN+") (pinfunction "IN+_IN+") (pintype "bidirectional"))
    )
    (net (code "43") (name "VCC_BBANK") (class "Default")
      (node (ref "BBANK") (pin "1") (pinfunction "1_1") (pintype "bidirectional"))
      (node (ref "R5") (pin "1") (pinfunction "1_1") (pintype "passive"))
    )
    (net (code "44") (name "VCC_PV") (class "Default")
      (node (ref "R7") (pin "1") (pinfunction "1_1") (pintype "passive"))
      (node (ref "VPV") (pin "1") (pinfunction "1_1") (pintype "bidirectional"))
    )
    (net (code "45") (name "unconnected-(IC1-NC-Pad4)") (class "Default")
      (node (ref "IC1") (pin "4") (pinfunction "NC_4") (pintype "no_connect"))
    )
    (net (code "46") (name "unconnected-(IC5-ALERT{slash}RDY-Pad2)") (class "Default")
      (node (ref "IC5") (pin "2") (pinfunction "ALERT/RDY_2") (pintype "bidirectional"))
    )
    (net (code "47") (name "~{RXEN}") (class "Default")
      (node (ref "IC7") (pin "2") (pinfunction "~{RE}_2") (pintype "bidirectional"))
      (node (ref "R12") (pin "1") (pinfunction "1_1") (pintype "passive"))
      (node (ref "U$1") (pin "23") (pinfunction "23_23") (pintype "bidirectional"))
    )
  )
)
